# BNSK-Rambo-Converters-Device.net
KiCad netlist of a schematic drawn in EAGLE
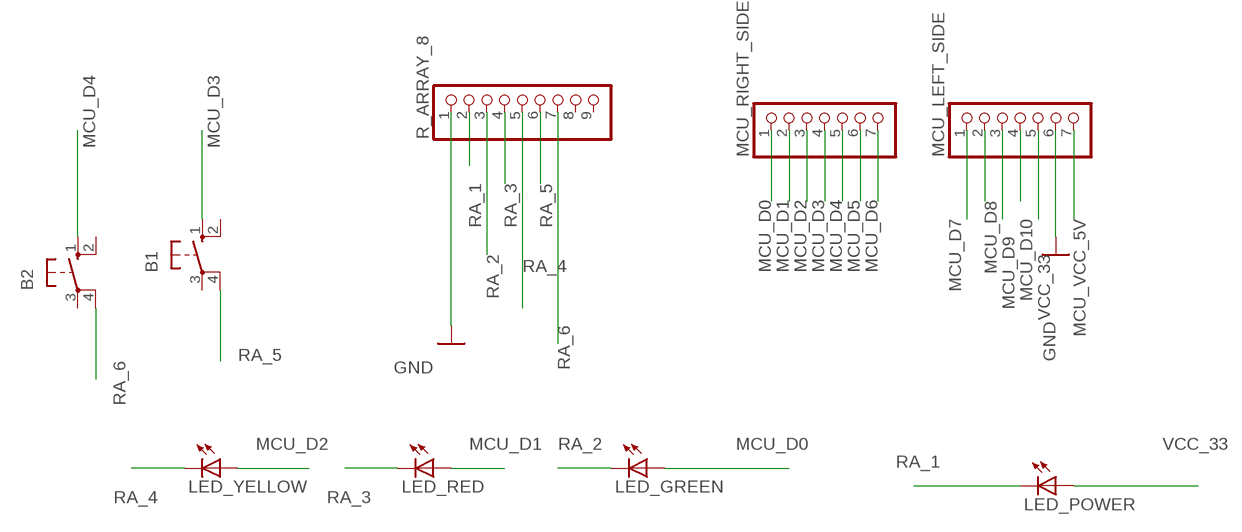
[diagram p0: schematic, sheet 1]

(export (version "E")
  (design (tool "Eeschema 10.0.6"))
  (components
    (comp (ref "B1")
      (value "10-XX")
      (footprint "eagle-import:B3F-10XX")
      (fields (field (name "MPN") "B3F-1000"))
      (libsource (lib "eagle-import") (part "10-XX"))
    )
    (comp (ref "B2")
      (value "10-XX")
      (footprint "eagle-import:B3F-10XX")
      (fields (field (name "MPN") "B3F-1000"))
      (libsource (lib "eagle-import") (part "10-XX"))
    )
    (comp (ref "LED_GREEN")
      (value "LEDSMT1206")
      (footprint "eagle-import:1206")
      (libsource (lib "eagle-import") (part "LEDSMT1206"))
    )
    (comp (ref "LED_POWER")
      (value "LEDSMT1206")
      (footprint "eagle-import:1206")
      (libsource (lib "eagle-import") (part "LEDSMT1206"))
    )
    (comp (ref "LED_RED")
      (value "LEDSMT1206")
      (footprint "eagle-import:1206")
      (libsource (lib "eagle-import") (part "LEDSMT1206"))
    )
    (comp (ref "LED_YELLOW")
      (value "LEDSMT1206")
      (footprint "eagle-import:1206")
      (libsource (lib "eagle-import") (part "LEDSMT1206"))
    )
    (comp (ref "MCU_LEFT_SIDE")
      (value "PINHD-1X7")
      (footprint "eagle-import:1X07")
      (libsource (lib "eagle-import") (part "PINHD-1X7"))
    )
    (comp (ref "MCU_RIGHT_SIDE")
      (value "PINHD-1X7")
      (footprint "eagle-import:1X07")
      (libsource (lib "eagle-import") (part "PINHD-1X7"))
    )
    (comp (ref "R_ARRAY_8")
      (value "PINHD-1X9")
      (footprint "eagle-import:1X09-BIG")
      (libsource (lib "eagle-import") (part "PINHD-1X9"))
    )
  )
  (nets
    (net (code "1") (name "/MCU_D0") (class "Default")
      (node (ref "LED_GREEN") (pin "A") (pinfunction "A_A") (pintype "passive"))
      (node (ref "MCU_RIGHT_SIDE") (pin "1") (pinfunction "1_1") (pintype "passive"))
    )
    (net (code "2") (name "/MCU_D1") (class "Default")
      (node (ref "LED_RED") (pin "A") (pinfunction "A_A") (pintype "passive"))
      (node (ref "MCU_RIGHT_SIDE") (pin "2") (pinfunction "2_2") (pintype "passive"))
    )
    (net (code "3") (name "/MCU_D2") (class "Default")
      (node (ref "LED_YELLOW") (pin "A") (pinfunction "A_A") (pintype "passive"))
      (node (ref "MCU_RIGHT_SIDE") (pin "3") (pinfunction "3_3") (pintype "passive"))
    )
    (net (code "4") (name "/MCU_D3") (class "Default")
      (node (ref "B1") (pin "1") (pinfunction "S_1") (pintype "passive"))
      (node (ref "MCU_RIGHT_SIDE") (pin "4") (pinfunction "4_4") (pintype "passive"))
    )
    (net (code "5") (name "/MCU_D4") (class "Default")
      (node (ref "B2") (pin "1") (pinfunction "S_1") (pintype "passive"))
      (node (ref "MCU_RIGHT_SIDE") (pin "5") (pinfunction "5_5") (pintype "passive"))
    )
    (net (code "6") (name "/MCU_D5") (class "Default")
      (node (ref "MCU_RIGHT_SIDE") (pin "6") (pinfunction "6_6") (pintype "passive"))
    )
    (net (code "7") (name "/MCU_D6") (class "Default")
      (node (ref "MCU_RIGHT_SIDE") (pin "7") (pinfunction "7_7") (pintype "passive"))
    )
    (net (code "8") (name "/MCU_D7") (class "Default")
      (node (ref "MCU_LEFT_SIDE") (pin "1") (pinfunction "1_1") (pintype "passive"))
    )
    (net (code "9") (name "/MCU_D8") (class "Default")
      (node (ref "MCU_LEFT_SIDE") (pin "2") (pinfunction "2_2") (pintype "passive"))
    )
    (net (code "10") (name "/MCU_D9") (class "Default")
      (node (ref "MCU_LEFT_SIDE") (pin "3") (pinfunction "3_3") (pintype "passive"))
    )
    (net (code "11") (name "/MCU_D10") (class "Default")
      (node (ref "MCU_LEFT_SIDE") (pin "4") (pinfunction "4_4") (pintype "passive"))
    )
    (net (code "12") (name "/MCU_VCC_5V") (class "Default")
      (node (ref "MCU_LEFT_SIDE") (pin "7") (pinfunction "7_7") (pintype "passive"))
    )
    (net (code "13") (name "/RA_1") (class "Default")
      (node (ref "LED_POWER") (pin "C") (pinfunction "C_C") (pintype "passive"))
      (node (ref "R_ARRAY_8") (pin "2") (pinfunction "2_2") (pintype "passive"))
    )
    (net (code "14") (name "/RA_2") (class "Default")
      (node (ref "LED_GREEN") (pin "C") (pinfunction "C_C") (pintype "passive"))
      (node (ref "R_ARRAY_8") (pin "3") (pinfunction "3_3") (pintype "passive"))
    )
    (net (code "15") (name "/RA_3") (class "Default")
      (node (ref "LED_RED") (pin "C") (pinfunction "C_C") (pintype "passive"))
      (node (ref "R_ARRAY_8") (pin "4") (pinfunction "4_4") (pintype "passive"))
    )
    (net (code "16") (name "/RA_4") (class "Default")
      (node (ref "LED_YELLOW") (pin "C") (pinfunction "C_C") (pintype "passive"))
      (node (ref "R_ARRAY_8") (pin "5") (pinfunction "5_5") (pintype "passive"))
    )
    (net (code "17") (name "/RA_5") (class "Default")
      (node (ref "B1") (pin "4") (pinfunction "P1_4") (pintype "passive"))
      (node (ref "R_ARRAY_8") (pin "6") (pinfunction "6_6") (pintype "passive"))
    )
    (net (code "18") (name "/RA_6") (class "Default")
      (node (ref "B2") (pin "4") (pinfunction "P1_4") (pintype "passive"))
      (node (ref "R_ARRAY_8") (pin "7") (pinfunction "7_7") (pintype "passive"))
    )
    (net (code "19") (name "/VCC_33") (class "Default")
      (node (ref "LED_POWER") (pin "A") (pinfunction "A_A") (pintype "passive"))
      (node (ref "MCU_LEFT_SIDE") (pin "5") (pinfunction "5_5") (pintype "passive"))
    )
    (net (code "20") (name "GND") (class "Default")
      (node (ref "MCU_LEFT_SIDE") (pin "6") (pinfunction "6_6") (pintype "passive"))
      (node (ref "R_ARRAY_8") (pin "1") (pinfunction "1_1") (pintype "passive"))
    )
    (net (code "21") (name "unconnected-(B1-P-Pad3)") (class "Default")
      (node (ref "B1") (pin "3") (pinfunction "P_3") (pintype "passive"))
    )
    (net (code "22") (name "unconnected-(B1-S1-Pad2)") (class "Default")
      (node (ref "B1") (pin "2") (pinfunction "S1_2") (pintype "passive"))
    )
    (net (code "23") (name "unconnected-(B2-P-Pad3)") (class "Default")
      (node (ref "B2") (pin "3") (pinfunction "P_3") (pintype "passive"))
    )
    (net (code "24") (name "unconnected-(B2-S1-Pad2)") (class "Default")
      (node (ref "B2") (pin "2") (pinfunction "S1_2") (pintype "passive"))
    )
    (net (code "25") (name "unconnected-(R_ARRAY_8-Pad8)") (class "Default")
      (node (ref "R_ARRAY_8") (pin "8") (pinfunction "8_8") (pintype "passive"))
    )
    (net (code "26") (name "unconnected-(R_ARRAY_8-Pad9)") (class "Default")
      (node (ref "R_ARRAY_8") (pin "9") (pinfunction "9_9") (pintype "passive"))
    )
  )
)
